# Motor-E.net
KiCad netlist of a schematic drawn in Altium Designer
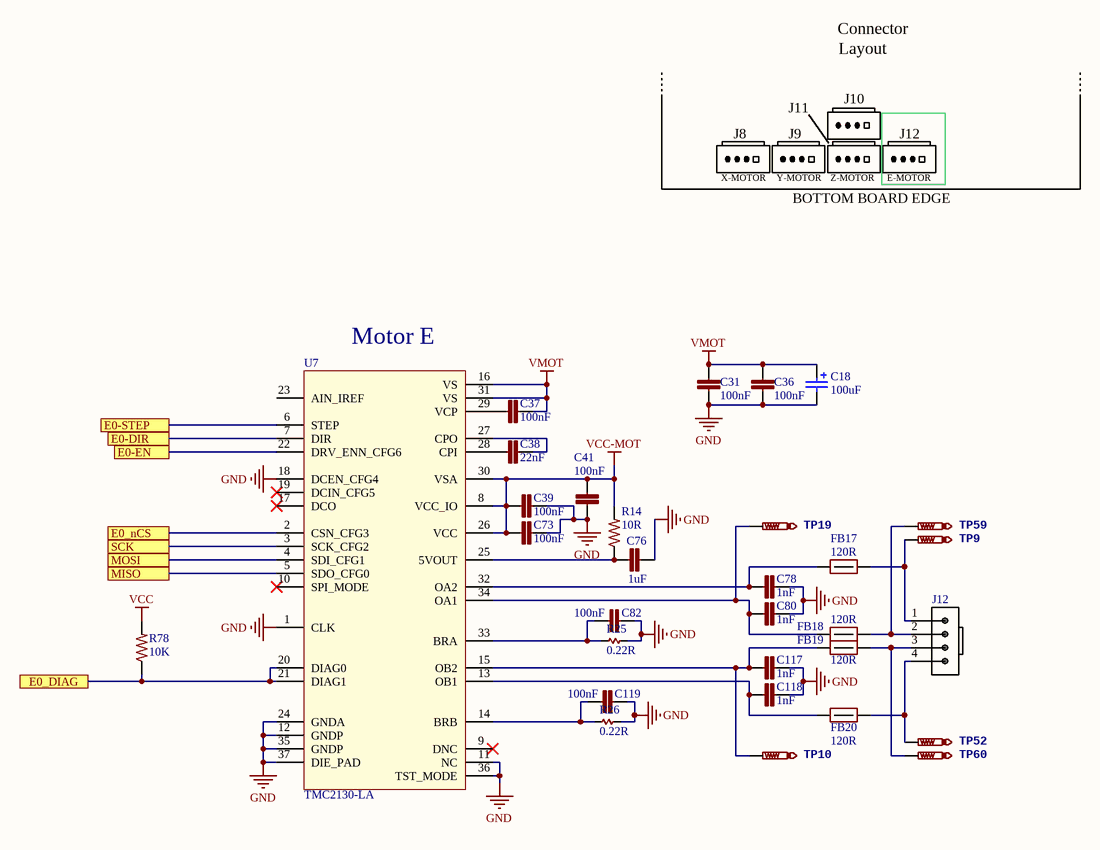
[diagram p0: Motor-E.SchDoc]

(export (version "E")
  (design (tool "Eeschema 10.0.6"))
  (components
    (comp (ref "C18")
      (value "100uF")
      (footprint "CAP-ELEC-063063077")
      (description "CAP ALUM 100UF 35V 20% SMD")
      (fields (field (name "MANUFACTURER") "Nichicon") (field (name "TOLERANCE") "+/- 20%"))
      (libsource (lib "3Delight") (part "UWT1V101MCL1GS"))
    )
    (comp (ref "C31")
      (value "100nF")
      (footprint "C0603")
      (description "CAP CER 0603 100nF 50V 10% X7R")
      (fields (field (name "MANUFACTURER") "Kemet") (field (name "TOLERANCE") "+/- 10%"))
      (libsource (lib "") (part "C0603C104K5RACTU_1"))
    )
    (comp (ref "C36")
      (value "100nF")
      (footprint "C0603")
      (description "CAP CER 0603 100nF 50V 10% X7R")
      (fields (field (name "MANUFACTURER") "Kemet") (field (name "TOLERANCE") "+/- 10%"))
      (libsource (lib "") (part "C0603C104K5RACTU_1"))
    )
    (comp (ref "C37")
      (value "100nF")
      (footprint "C0603")
      (description "CAP CER 0603 100nF 50V 10% X7R")
      (fields (field (name "MANUFACTURER") "Kemet") (field (name "TOLERANCE") "+/- 10%"))
      (libsource (lib "") (part "C0603C104K5RACTU_2"))
    )
    (comp (ref "C38")
      (value "22nF")
      (footprint "C0402")
      (description "CAP CER 0402 22nF ±10% 50V X7R")
      (fields (field (name "MANUFACTURER") "YAGEO") (field (name "TOLERANCE") "+/- 10%"))
      (libsource (lib "3Delight") (part "GCM155R71H223KA55D"))
    )
    (comp (ref "C39")
      (value "100nF")
      (footprint "C0402")
      (description "CAP CER 0402 100nF 16V 10% X7R")
      (fields (field (name "MANUFACTURER") "Murata") (field (name "TOLERANCE") "+/- 10%"))
      (libsource (lib "3Delight") (part "GRM155R71C104KA88D"))
    )
    (comp (ref "C41")
      (value "100nF")
      (footprint "C0402")
      (description "CAP CER 0402 100nF 16V 10% X7R")
      (fields (field (name "MANUFACTURER") "Murata") (field (name "TOLERANCE") "+/- 10%"))
      (libsource (lib "") (part "GRM155R71C104KA88D_1"))
    )
    (comp (ref "C73")
      (value "100nF")
      (footprint "C0402")
      (description "CAP CER 0402 100nF 16V 10% X7R")
      (fields (field (name "MANUFACTURER") "Murata") (field (name "TOLERANCE") "+/- 10%"))
      (libsource (lib "3Delight") (part "GRM155R71C104KA88D"))
    )
    (comp (ref "C76")
      (value "1uF")
      (footprint "C0402")
      (description "CAP CER 0402 1uF 6.3V 10% X5R")
      (fields (field (name "MANUFACTURER") "Murata") (field (name "TOLERANCE") "+/- 10%"))
      (libsource (lib "3Delight") (part "GRM155R60J105KE19D"))
    )
    (comp (ref "C78")
      (value "1nF")
      (footprint "C0603")
      (description "CAP CER 0603  1nF 50v 10% X7R")
      (fields (field (name "MANUFACTURER") "Kemet") (field (name "TOLERANCE") "+/- 10%"))
      (libsource (lib "3Delight") (part "C0603C102K5RACTU"))
    )
    (comp (ref "C80")
      (value "1nF")
      (footprint "C0603")
      (description "CAP CER 0603  1nF 50v 10% X7R")
      (fields (field (name "MANUFACTURER") "Kemet") (field (name "TOLERANCE") "+/- 10%"))
      (libsource (lib "3Delight") (part "C0603C102K5RACTU"))
    )
    (comp (ref "C82")
      (value "100nF")
      (footprint "C0603")
      (description "CAP CER 0603 100nF 50V 10% X7R")
      (fields (field (name "MANUFACTURER") "Kemet") (field (name "TOLERANCE") "+/- 10%"))
      (libsource (lib "3Delight") (part "C0603C104K5RACTU"))
    )
    (comp (ref "C117")
      (value "1nF")
      (footprint "C0603")
      (description "CAP CER 0603  1nF 50v 10% X7R")
      (fields (field (name "MANUFACTURER") "Kemet") (field (name "TOLERANCE") "+/- 10%"))
      (libsource (lib "3Delight") (part "C0603C102K5RACTU"))
    )
    (comp (ref "C118")
      (value "1nF")
      (footprint "C0603")
      (description "CAP CER 0603  1nF 50v 10% X7R")
      (fields (field (name "MANUFACTURER") "Kemet") (field (name "TOLERANCE") "+/- 10%"))
      (libsource (lib "3Delight") (part "C0603C102K5RACTU"))
    )
    (comp (ref "C119")
      (value "100nF")
      (footprint "C0603")
      (description "CAP CER 0603 100nF 50V 10% X7R")
      (fields (field (name "MANUFACTURER") "Kemet") (field (name "TOLERANCE") "+/- 10%"))
      (libsource (lib "3Delight") (part "C0603C104K5RACTU"))
    )
    (comp (ref "FB17")
      (value "120R")
      (footprint "FB0603")
      (description "FERRITE BEAD 120 OHM 0603 1LN")
      (fields (field (name "MANUFACTURER") "Samsung") (field (name "PART") "FERRITE 120R 3A 0603"))
      (libsource (lib "Inductors") (part "FERRITE 120R 3A 0603"))
    )
    (comp (ref "FB18")
      (value "120R")
      (footprint "FB0603")
      (description "FERRITE BEAD 120 OHM 0603 1LN")
      (fields (field (name "MANUFACTURER") "Samsung") (field (name "PART") "FERRITE 120R 3A 0603"))
      (libsource (lib "Inductors") (part "FERRITE 120R 3A 0603"))
    )
    (comp (ref "FB19")
      (value "120R")
      (footprint "FB0603")
      (description "FERRITE BEAD 120 OHM 0603 1LN")
      (fields (field (name "MANUFACTURER") "Samsung") (field (name "PART") "FERRITE 120R 3A 0603"))
      (libsource (lib "Inductors") (part "FERRITE 120R 3A 0603"))
    )
    (comp (ref "FB20")
      (value "120R")
      (footprint "FB0603")
      (description "FERRITE BEAD 120 OHM 0603 1LN")
      (fields (field (name "MANUFACTURER") "Samsung") (field (name "PART") "FERRITE 120R 3A 0603"))
      (libsource (lib "Inductors") (part "FERRITE 120R 3A 0603"))
    )
    (comp (ref "J12")
      (value "Molex 0705430003")
      (footprint "4POL254 PIN-IN-PASTE")
      (description "Molex 4 Pin Clip Connector")
      (libsource (lib "Connectors") (part "Molex 0705430003 PIN-IN-PASTE"))
    )
    (comp (ref "R14")
      (value "10R")
      (footprint "R0402")
      (description "RES SMD 10 OHM 1% 1/16W 0402")
      (fields (field (name "MANUFACTURER") "Yageo") (field (name "TOLERANCE") "+/- 1%"))
      (libsource (lib "3Delight") (part "RC0402FR-0710RL"))
    )
    (comp (ref "R25")
      (value "0.22R")
      (footprint "R1206")
      (description "RES SMD 0.22 OHM 1% 1/3W 1206")
      (fields (field (name "MANUFACTURER") "Panasonic") (field (name "TOLERANCE") "+/- 1%"))
      (libsource (lib "Resistors") (part "0.22R 1% 1206"))
    )
    (comp (ref "R26")
      (value "0.22R")
      (footprint "R1206")
      (description "RES SMD 0.22 OHM 1% 1/3W 1206")
      (fields (field (name "MANUFACTURER") "Panasonic") (field (name "TOLERANCE") "+/- 1%"))
      (libsource (lib "Resistors") (part "0.22R 1% 1206"))
    )
    (comp (ref "R78")
      (value "10K")
      (footprint "R0402")
      (description "RES SMD 10K OHM 1% 1/16W 0402")
      (fields (field (name "MANUFACTURER") "Yageo") (field (name "PART") "10k 1% 0402"))
      (libsource (lib "3Delight") (part "RC0402FR-0710KP"))
    )
    (comp (ref "TP9")
      (value "TestPoint")
      (footprint "TP1-27")
      (description "Test Point")
      (libsource (lib "3Delight") (part "TestPoint"))
    )
    (comp (ref "TP10")
      (value "TestPoint")
      (footprint "TP1-27")
      (description "Test Point")
      (libsource (lib "3Delight") (part "TestPoint"))
    )
    (comp (ref "TP19")
      (value "TestPoint")
      (footprint "TP1-27")
      (description "Test Point")
      (libsource (lib "3Delight") (part "TestPoint"))
    )
    (comp (ref "TP52")
      (value "TestPoint")
      (footprint "TP1-27")
      (description "Test Point")
      (libsource (lib "3Delight") (part "TestPoint"))
    )
    (comp (ref "TP59")
      (value "TestPoint")
      (footprint "TP1-27")
      (description "Test Point")
      (libsource (lib "3Delight") (part "TestPoint"))
    )
    (comp (ref "TP60")
      (value "TestPoint")
      (footprint "TP1-27")
      (description "Test Point")
      (libsource (lib "3Delight") (part "TestPoint"))
    )
    (comp (ref "U7")
      (value "TMC2130-LA")
      (footprint "QFN36-DualSolderMask")
      (description "IC STEPPER MOTOR DVR SPI 36QFN")
      (fields (field (name "MANUFACTURER") "Trinamic") (field (name "PART") "TMC2130"))
      (libsource (lib "ICs-Motor Controller") (part "TMC2130-DualSolderMask"))
    )
  )
  (nets
    (net (code "1") (name "/E0-DIR") (class "Default")
      (node (ref "U7") (pin "7") (pinfunction "DIR_7") (pintype "passive"))
    )
    (net (code "2") (name "/E0-EN") (class "Default")
      (node (ref "U7") (pin "22") (pinfunction "DRV_ENN_CFG6_22") (pintype "passive"))
    )
    (net (code "3") (name "/E0-STEP") (class "Default")
      (node (ref "U7") (pin "6") (pinfunction "STEP_6") (pintype "passive"))
    )
    (net (code "4") (name "/E0_DIAG") (class "Default")
      (node (ref "R78") (pin "1") (pinfunction "1_1") (pintype "passive"))
      (node (ref "U7") (pin "20") (pinfunction "DIAG0_20") (pintype "passive"))
      (node (ref "U7") (pin "21") (pinfunction "DIAG1_21") (pintype "passive"))
    )
    (net (code "5") (name "/E0_nCS") (class "Default")
      (node (ref "U7") (pin "2") (pinfunction "CSN_CFG3_2") (pintype "passive"))
    )
    (net (code "6") (name "/MISO") (class "Default")
      (node (ref "U7") (pin "5") (pinfunction "SDO_CFG0_5") (pintype "passive"))
    )
    (net (code "7") (name "/MOSI") (class "Default")
      (node (ref "U7") (pin "4") (pinfunction "SDI_CFG1_4") (pintype "passive"))
    )
    (net (code "8") (name "/SCK") (class "Default")
      (node (ref "U7") (pin "3") (pinfunction "SCK_CFG2_3") (pintype "passive"))
    )
    (net (code "9") (name "GND") (class "Default")
      (node (ref "C117") (pin "2") (pinfunction "2_2") (pintype "passive"))
      (node (ref "C118") (pin "2") (pinfunction "2_2") (pintype "passive"))
      (node (ref "C119") (pin "1") (pinfunction "1_1") (pintype "passive"))
      (node (ref "C18") (pin "2") (pinfunction "2_2") (pintype "passive"))
      (node (ref "C31") (pin "1") (pinfunction "1_1") (pintype "passive"))
      (node (ref "C36") (pin "1") (pinfunction "1_1") (pintype "passive"))
      (node (ref "C39") (pin "1") (pinfunction "1_1") (pintype "passive"))
      (node (ref "C41") (pin "1") (pinfunction "1_1") (pintype "passive"))
      (node (ref "C73") (pin "1") (pinfunction "1_1") (pintype "passive"))
      (node (ref "C76") (pin "2") (pinfunction "2_2") (pintype "passive"))
      (node (ref "C78") (pin "2") (pinfunction "2_2") (pintype "passive"))
      (node (ref "C80") (pin "2") (pinfunction "2_2") (pintype "passive"))
      (node (ref "C82") (pin "1") (pinfunction "1_1") (pintype "passive"))
      (node (ref "R25") (pin "2") (pinfunction "2_2") (pintype "passive"))
      (node (ref "R26") (pin "2") (pinfunction "2_2") (pintype "passive"))
      (node (ref "U7") (pin "1") (pinfunction "CLK_1") (pintype "passive"))
      (node (ref "U7") (pin "11") (pinfunction "NC_11") (pintype "passive"))
      (node (ref "U7") (pin "12") (pinfunction "GNDP_12") (pintype "passive"))
      (node (ref "U7") (pin "18") (pinfunction "DCEN_CFG4_18") (pintype "passive"))
      (node (ref "U7") (pin "24") (pinfunction "GNDA_24") (pintype "passive"))
      (node (ref "U7") (pin "35") (pinfunction "GNDP_35") (pintype "passive"))
      (node (ref "U7") (pin "36") (pinfunction "TST_MODE_36") (pintype "passive"))
      (node (ref "U7") (pin "37") (pinfunction "DIE_PAD_37") (pintype "passive"))
    )
    (net (code "10") (name "Net-(FB17-Pad2)") (class "Default")
      (node (ref "FB17") (pin "2") (pinfunction "2_2") (pintype "passive"))
      (node (ref "J12") (pin "1") (pinfunction "1_1") (pintype "passive"))
      (node (ref "TP9") (pin "TP") (pinfunction "TP_TP") (pintype "passive"))
    )
    (net (code "11") (name "Net-(FB18-Pad2)") (class "Default")
      (node (ref "FB18") (pin "2") (pinfunction "2_2") (pintype "passive"))
      (node (ref "J12") (pin "2") (pinfunction "2_2") (pintype "passive"))
      (node (ref "TP59") (pin "TP") (pinfunction "TP_TP") (pintype "passive"))
    )
    (net (code "12") (name "Net-(FB19-Pad2)") (class "Default")
      (node (ref "FB19") (pin "2") (pinfunction "2_2") (pintype "passive"))
      (node (ref "J12") (pin "3") (pinfunction "3_3") (pintype "passive"))
      (node (ref "TP60") (pin "TP") (pinfunction "TP_TP") (pintype "passive"))
    )
    (net (code "13") (name "Net-(FB20-Pad2)") (class "Default")
      (node (ref "FB20") (pin "2") (pinfunction "2_2") (pintype "passive"))
      (node (ref "J12") (pin "4") (pinfunction "4_4") (pintype "passive"))
      (node (ref "TP52") (pin "TP") (pinfunction "TP_TP") (pintype "passive"))
    )
    (net (code "14") (name "Net-(U7-5VOUT)") (class "Default")
      (node (ref "C76") (pin "1") (pinfunction "1_1") (pintype "passive"))
      (node (ref "R14") (pin "1") (pinfunction "1_1") (pintype "passive"))
      (node (ref "U7") (pin "25") (pinfunction "5VOUT_25") (pintype "passive"))
    )
    (net (code "15") (name "Net-(U7-BRA)") (class "Default")
      (node (ref "C82") (pin "2") (pinfunction "2_2") (pintype "passive"))
      (node (ref "R25") (pin "1") (pinfunction "1_1") (pintype "passive"))
      (node (ref "U7") (pin "33") (pinfunction "BRA_33") (pintype "passive"))
    )
    (net (code "16") (name "Net-(U7-BRB)") (class "Default")
      (node (ref "C119") (pin "2") (pinfunction "2_2") (pintype "passive"))
      (node (ref "R26") (pin "1") (pinfunction "1_1") (pintype "passive"))
      (node (ref "U7") (pin "14") (pinfunction "BRB_14") (pintype "passive"))
    )
    (net (code "17") (name "Net-(U7-CPI)") (class "Default")
      (node (ref "C38") (pin "1") (pinfunction "1_1") (pintype "passive"))
      (node (ref "U7") (pin "28") (pinfunction "CPI_28") (pintype "passive"))
    )
    (net (code "18") (name "Net-(U7-CPO)") (class "Default")
      (node (ref "C38") (pin "2") (pinfunction "2_2") (pintype "passive"))
      (node (ref "U7") (pin "27") (pinfunction "CPO_27") (pintype "passive"))
    )
    (net (code "19") (name "Net-(U7-OA1)") (class "Default")
      (node (ref "C80") (pin "1") (pinfunction "1_1") (pintype "passive"))
      (node (ref "FB18") (pin "1") (pinfunction "1_1") (pintype "passive"))
      (node (ref "TP19") (pin "TP") (pinfunction "TP_TP") (pintype "passive"))
      (node (ref "U7") (pin "34") (pinfunction "OA1_34") (pintype "passive"))
    )
    (net (code "20") (name "Net-(U7-OA2)") (class "Default")
      (node (ref "C78") (pin "1") (pinfunction "1_1") (pintype "passive"))
      (node (ref "FB17") (pin "1") (pinfunction "1_1") (pintype "passive"))
      (node (ref "U7") (pin "32") (pinfunction "OA2_32") (pintype "passive"))
    )
    (net (code "21") (name "Net-(U7-OB1)") (class "Default")
      (node (ref "C118") (pin "1") (pinfunction "1_1") (pintype "passive"))
      (node (ref "FB20") (pin "1") (pinfunction "1_1") (pintype "passive"))
      (node (ref "U7") (pin "13") (pinfunction "OB1_13") (pintype "passive"))
    )
    (net (code "22") (name "Net-(U7-OB2)") (class "Default")
      (node (ref "C117") (pin "1") (pinfunction "1_1") (pintype "passive"))
      (node (ref "FB19") (pin "1") (pinfunction "1_1") (pintype "passive"))
      (node (ref "TP10") (pin "TP") (pinfunction "TP_TP") (pintype "passive"))
      (node (ref "U7") (pin "15") (pinfunction "OB2_15") (pintype "passive"))
    )
    (net (code "23") (name "Net-(U7-VCP)") (class "Default")
      (node (ref "C37") (pin "1") (pinfunction "1_1") (pintype "passive"))
      (node (ref "U7") (pin "29") (pinfunction "VCP_29") (pintype "passive"))
    )
    (net (code "24") (name "VCC") (class "Default")
      (node (ref "R78") (pin "2") (pinfunction "2_2") (pintype "passive"))
    )
    (net (code "25") (name "VCC-MOT") (class "Default")
      (node (ref "C39") (pin "2") (pinfunction "2_2") (pintype "passive"))
      (node (ref "C41") (pin "2") (pinfunction "2_2") (pintype "passive"))
      (node (ref "C73") (pin "2") (pinfunction "2_2") (pintype "passive"))
      (node (ref "R14") (pin "2") (pinfunction "2_2") (pintype "passive"))
      (node (ref "U7") (pin "26") (pinfunction "VCC_26") (pintype "passive"))
      (node (ref "U7") (pin "30") (pinfunction "VSA_30") (pintype "passive"))
      (node (ref "U7") (pin "8") (pinfunction "VCC_IO_8") (pintype "passive"))
    )
    (net (code "26") (name "VMOT") (class "Default")
      (node (ref "C18") (pin "1") (pinfunction "1_1") (pintype "passive"))
      (node (ref "C31") (pin "2") (pinfunction "2_2") (pintype "passive"))
      (node (ref "C36") (pin "2") (pinfunction "2_2") (pintype "passive"))
      (node (ref "C37") (pin "2") (pinfunction "2_2") (pintype "passive"))
      (node (ref "U7") (pin "16") (pinfunction "VS_16") (pintype "passive"))
      (node (ref "U7") (pin "31") (pinfunction "VS_31") (pintype "passive"))
    )
    (net (code "27") (name "unconnected-(U7-AIN_IREF-Pad23)") (class "Default")
      (node (ref "U7") (pin "23") (pinfunction "AIN_IREF_23") (pintype "passive"))
    )
    (net (code "28") (name "unconnected-(U7-DCIN_CFG5-Pad19)") (class "Default")
      (node (ref "U7") (pin "19") (pinfunction "DCIN_CFG5_19") (pintype "passive+no_connect"))
    )
    (net (code "29") (name "unconnected-(U7-DCO-Pad17)") (class "Default")
      (node (ref "U7") (pin "17") (pinfunction "DCO_17") (pintype "passive+no_connect"))
    )
    (net (code "30") (name "unconnected-(U7-DNC-Pad9)") (class "Default")
      (node (ref "U7") (pin "9") (pinfunction "DNC_9") (pintype "passive+no_connect"))
    )
    (net (code "31") (name "unconnected-(U7-SPI_MODE-Pad10)") (class "Default")
      (node (ref "U7") (pin "10") (pinfunction "SPI_MODE_10") (pintype "passive+no_connect"))
    )
  )
)
